# main.net
KiCad netlist of a schematic drawn in Altium Designer
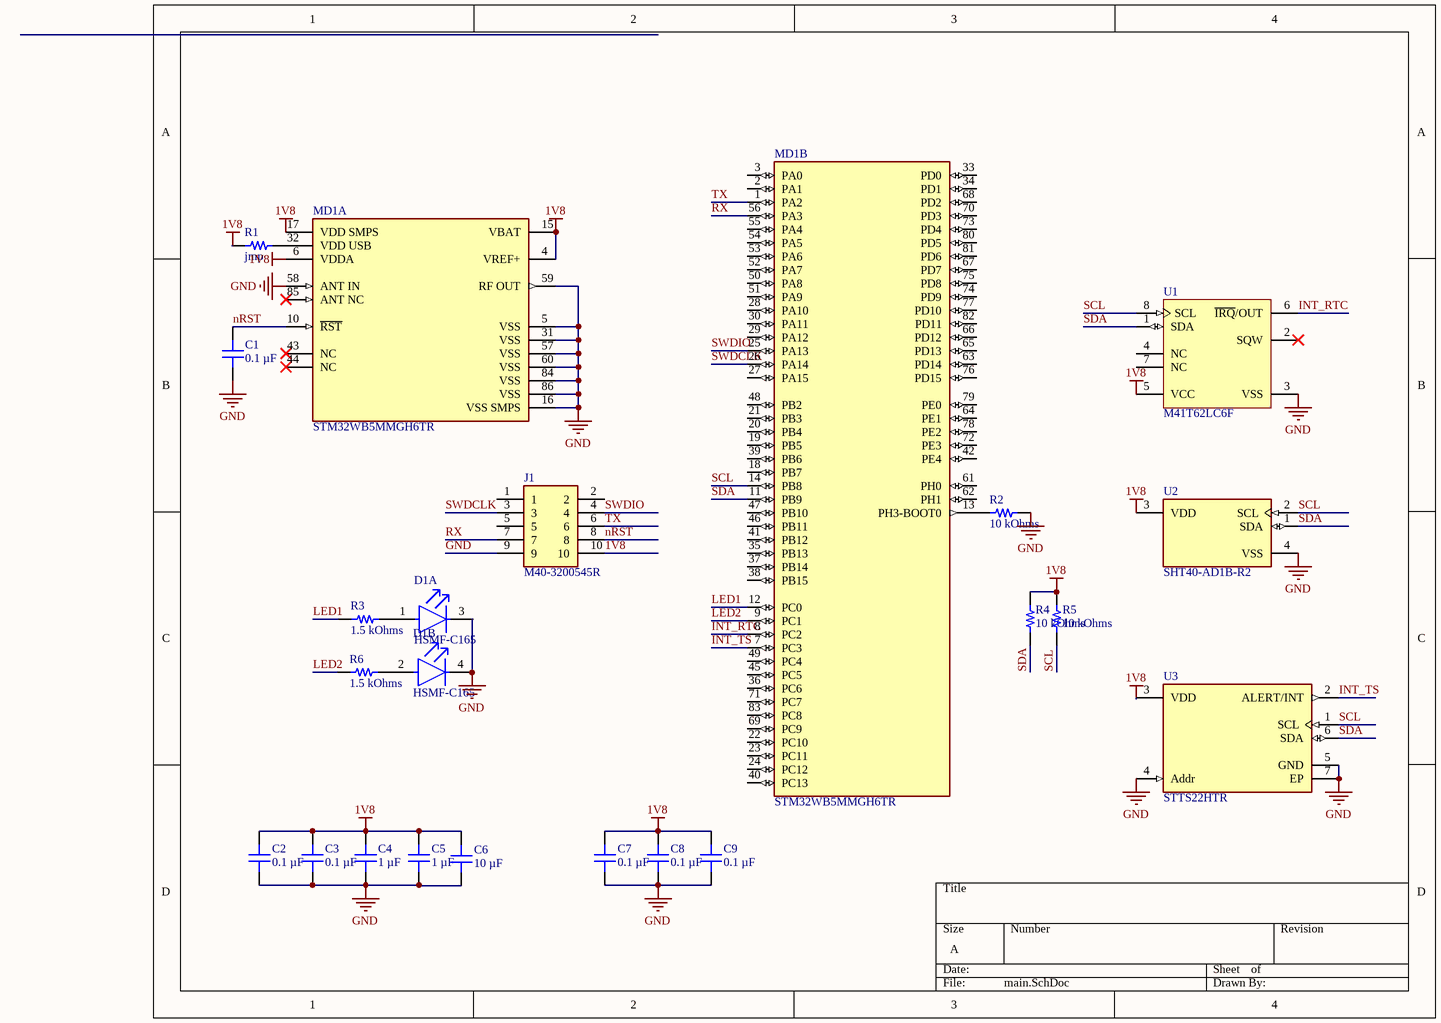
[diagram p0: main.SchDoc]

(export (version "E")
  (design (tool "Eeschema 10.0.6"))
  (components
    (comp (ref "C1")
      (value "0.1 µF")
      (footprint "CAP 0402_1005")
      (description "CAP CER 0.1UF 4V X5R 0402")
      (fields (field (name "PART NUMBER") "C0402C104K7PAC7867") (field (name "MANUFACTURER") "KEMET"))
      (libsource (lib "Celestial Altium Library - altium_library") (part "Capacitor"))
    )
    (comp (ref "C2")
      (value "0.1 µF")
      (footprint "CAP 0402_1005")
      (description "CAP CER 0.1UF 4V X5R 0402")
      (fields (field (name "PART NUMBER") "C0402C104K7PAC7867") (field (name "MANUFACTURER") "KEMET"))
      (libsource (lib "Celestial Altium Library - altium_library") (part "Capacitor"))
    )
    (comp (ref "C3")
      (value "0.1 µF")
      (footprint "CAP 0402_1005")
      (description "CAP CER 0402 0.1UF 16V X7R 10%")
      (fields (field (name "PART NUMBER") "C0402C104K4RECAUTO") (field (name "MANUFACTURER") "KEMET"))
      (libsource (lib "Celestial Altium Library - altium_library") (part "Capacitor"))
    )
    (comp (ref "C4")
      (value "1 µF")
      (footprint "CAP 0402_1005")
      (description "CAP CER 1UF 10V X5R 0402")
      (fields (field (name "PART NUMBER") "LMK105BJ105MVHF") (field (name "MANUFACTURER") "Taiyo Yuden"))
      (libsource (lib "Celestial Altium Library - altium_library") (part "Capacitor"))
    )
    (comp (ref "C5")
      (value "1 µF")
      (footprint "CAP 0402_1005")
      (description "CAP CER 1UF 10V X5R 0402")
      (fields (field (name "PART NUMBER") "LMK105BJ105MVHF") (field (name "MANUFACTURER") "Taiyo Yuden"))
      (libsource (lib "Celestial Altium Library - altium_library") (part "Capacitor"))
    )
    (comp (ref "C6")
      (value "10 µF")
      (footprint "CAP 0603_1608")
      (description "CAP CER 10UF 6.3V X5R 0603")
      (fields
        (field (name "PART NUMBER") "GRM188R60J106ME47D")
        (field (name "MANUFACTURER") "Murata Electronics")
      )
      (libsource (lib "Celestial Altium Library - altium_library") (part "Capacitor"))
    )
    (comp (ref "C7")
      (value "0.1 µF")
      (footprint "CAP 0402_1005")
      (description "CAP CER 0402 0.1UF 16V X7R 10%")
      (fields (field (name "PART NUMBER") "C0402C104K4RECAUTO") (field (name "MANUFACTURER") "KEMET"))
      (libsource (lib "Celestial Altium Library - altium_library") (part "Capacitor"))
    )
    (comp (ref "C8")
      (value "0.1 µF")
      (footprint "CAP 0402_1005")
      (description "CAP CER 0.1UF 4V X5R 0402")
      (fields (field (name "PART NUMBER") "C0402C104K7PAC7867") (field (name "MANUFACTURER") "KEMET"))
      (libsource (lib "Celestial Altium Library - altium_library") (part "Capacitor"))
    )
    (comp (ref "C9")
      (value "0.1 µF")
      (footprint "CAP 0402_1005")
      (description "CAP CER 0.1UF 4V X5R 0402")
      (fields (field (name "PART NUMBER") "C0402C104K7PAC7867") (field (name "MANUFACTURER") "KEMET"))
      (libsource (lib "Celestial Altium Library - altium_library") (part "Capacitor"))
    )
    (comp (ref "D1")
      (value "HSMF-C165")
      (footprint "FP-HSMF-C165-MFG")
      (description "LED GREEN/RED DIFFUSED 0603 SMD")
      (libsource (lib "Altium Content Vault") (part "7c1fe340d8ce6b5db8c50b7ec3493de"))
    )
    (comp (ref "J1")
      (value "M40-3200545R")
      (footprint "HARWIN_M40-3200545R")
      (description "Connector Header Surface Mount 10 position 0.039 _1.00mm_")
      (fields (field (name "MF") "Harwin Inc."))
      (libsource (lib "M40-3200545R") (part "M40-3200545R"))
    )
    (comp (ref "MD1")
      (value "STM32WB5MMGH6TR")
      (footprint "FP-STM32WB5MMGH6TR-MFG")
      (description "ULTRA-LOW-POWER DUAL CORE ARM CO")
      (libsource (lib "Altium Content Vault") (part "634268d29c17b736a8286639810bf7d"))
    )
    (comp (ref "R1")
      (value "jmp")
      (footprint "RES 0402_1005")
      (description "RES 10K OHM 0.1% 1/10W 0402")
      (fields
        (field (name "PART NUMBER") "RP73PF1E10KBTD")
        (field (name "MANUFACTURER") "TE Connectivity Passive Product")
      )
      (libsource (lib "Celestial Altium Library - altium_library") (part "Resistor"))
    )
    (comp (ref "R2")
      (value "10 kOhms")
      (footprint "RES 0402_1005")
      (description "RES 10K OHM 0.1% 1/10W 0402")
      (fields
        (field (name "PART NUMBER") "RP73PF1E10KBTD")
        (field (name "MANUFACTURER") "TE Connectivity Passive Product")
      )
      (libsource (lib "Celestial Altium Library - altium_library") (part "Resistor"))
    )
    (comp (ref "R3")
      (value "1.5 kOhms")
      (footprint "RES 0402_1005")
      (description "RES 1.5K OHM 0.05% 1/10W 0402")
      (fields
        (field (name "PART NUMBER") "ERA-2VRW1501X")
        (field (name "MANUFACTURER") "Panasonic Electronic Components")
      )
      (libsource (lib "Celestial Altium Library - altium_library") (part "Resistor"))
    )
    (comp (ref "R4")
      (value "10 kOhms")
      (footprint "RES 0402_1005")
      (description "RES 10K OHM 0.1% 1/10W 0402")
      (fields
        (field (name "PART NUMBER") "RP73PF1E10KBTD")
        (field (name "MANUFACTURER") "TE Connectivity Passive Product")
      )
      (libsource (lib "Celestial Altium Library - altium_library") (part "Resistor"))
    )
    (comp (ref "R5")
      (value "10 kOhms")
      (footprint "RES 0402_1005")
      (description "RES 10K OHM 0.1% 1/10W 0402")
      (fields
        (field (name "PART NUMBER") "RP73PF1E10KBTD")
        (field (name "MANUFACTURER") "TE Connectivity Passive Product")
      )
      (libsource (lib "Celestial Altium Library - altium_library") (part "Resistor"))
    )
    (comp (ref "R6")
      (value "1.5 kOhms")
      (footprint "RES 0402_1005")
      (description "RES 1.5K OHM 0.05% 1/10W 0402")
      (fields
        (field (name "PART NUMBER") "ERA-2VRW1501X")
        (field (name "MANUFACTURER") "Panasonic Electronic Components")
      )
      (libsource (lib "Celestial Altium Library - altium_library") (part "Resistor"))
    )
    (comp (ref "U1")
      (value "M41T62LC6F")
      (footprint "STM-LCC8_V")
      (fields (field (name "MANUFACTURER") "STMicroelectronics"))
      (libsource (lib "Altium Content Vault") (part "STM-M41T62-LCC8"))
    )
    (comp (ref "U2")
      (value "SHT40-AD1B-R2")
      (footprint "FP-SHT40-AD1B-R2-MFG")
      (description "SENSOR HUMIDITY 100 RH SMD")
      (libsource (lib "Altium Content Vault") (part "985d6b895d3abb4f56b1b691ea450a8"))
    )
    (comp (ref "U3")
      (value "STTS22HTR")
      (footprint "FP-UDFN-6L-DM00423052-MFG")
      (description "LOW-VOLTAGE, ULTRA-LOW-POWER, 0.")
      (fields
        (field (name "OCTOPART") "https://octopart.com/stts22htr-stmicroelectronics-103417944")
        (field (name "MANUFACTURER") "STMicroelectronics")
      )
      (libsource (lib "Altium Content Vault") (part "a8cb2d3fb1f6f6cfa913d99606c4029"))
    )
  )
  (nets
    (net (code "1") (name "/INT_RTC") (class "Default")
      (node (ref "MD1") (pin "8") (pinfunction "PC2_8") (pintype "bidirectional"))
      (node (ref "U1") (pin "6") (pinfunction "~{IRQ}/OUT_6") (pintype "passive"))
    )
    (net (code "2") (name "/INT_TS") (class "Default")
      (node (ref "MD1") (pin "7") (pinfunction "PC3_7") (pintype "bidirectional"))
      (node (ref "U3") (pin "2") (pinfunction "ALERT/INT_2") (pintype "output"))
    )
    (net (code "3") (name "/LED1") (class "Default")
      (node (ref "MD1") (pin "12") (pinfunction "PC0_12") (pintype "bidirectional"))
      (node (ref "R3") (pin "2") (pinfunction "2_2") (pintype "passive"))
    )
    (net (code "4") (name "/LED2") (class "Default")
      (node (ref "MD1") (pin "9") (pinfunction "PC1_9") (pintype "bidirectional"))
      (node (ref "R6") (pin "2") (pinfunction "2_2") (pintype "passive"))
    )
    (net (code "5") (name "/RX") (class "Default")
      (node (ref "J1") (pin "7") (pinfunction "7_7") (pintype "passive"))
      (node (ref "MD1") (pin "56") (pinfunction "PA3_56") (pintype "bidirectional"))
    )
    (net (code "6") (name "/SCL") (class "Default")
      (node (ref "MD1") (pin "14") (pinfunction "PB8_14") (pintype "bidirectional"))
      (node (ref "R5") (pin "2") (pinfunction "2_2") (pintype "passive"))
      (node (ref "U1") (pin "8") (pinfunction "SCL_8") (pintype "input"))
      (node (ref "U2") (pin "2") (pinfunction "SCL_2") (pintype "input"))
      (node (ref "U3") (pin "1") (pinfunction "SCL_1") (pintype "input"))
    )
    (net (code "7") (name "/SDA") (class "Default")
      (node (ref "MD1") (pin "11") (pinfunction "PB9_11") (pintype "bidirectional"))
      (node (ref "R4") (pin "2") (pinfunction "2_2") (pintype "passive"))
      (node (ref "U1") (pin "1") (pinfunction "SDA_1") (pintype "bidirectional"))
      (node (ref "U2") (pin "1") (pinfunction "SDA_1") (pintype "bidirectional"))
      (node (ref "U3") (pin "6") (pinfunction "SDA_6") (pintype "bidirectional"))
    )
    (net (code "8") (name "/SWDCLK") (class "Default")
      (node (ref "J1") (pin "3") (pinfunction "3_3") (pintype "passive"))
      (node (ref "MD1") (pin "26") (pinfunction "PA14_26") (pintype "bidirectional"))
    )
    (net (code "9") (name "/SWDIO") (class "Default")
      (node (ref "J1") (pin "4") (pinfunction "4_4") (pintype "passive"))
      (node (ref "MD1") (pin "25") (pinfunction "PA13_25") (pintype "bidirectional"))
    )
    (net (code "10") (name "/TX") (class "Default")
      (node (ref "J1") (pin "6") (pinfunction "6_6") (pintype "passive"))
      (node (ref "MD1") (pin "1") (pinfunction "PA2_1") (pintype "bidirectional"))
    )
    (net (code "11") (name "/nRST") (class "Default")
      (node (ref "C1") (pin "1") (pinfunction "1_1") (pintype "passive"))
      (node (ref "J1") (pin "8") (pinfunction "8_8") (pintype "passive"))
      (node (ref "MD1") (pin "10") (pinfunction "~{RST}_10") (pintype "input"))
    )
    (net (code "12") (name "1V8") (class "Default")
      (node (ref "C2") (pin "2") (pinfunction "2_2") (pintype "passive"))
      (node (ref "C3") (pin "2") (pinfunction "2_2") (pintype "passive"))
      (node (ref "C4") (pin "2") (pinfunction "2_2") (pintype "passive"))
      (node (ref "C5") (pin "2") (pinfunction "2_2") (pintype "passive"))
      (node (ref "C6") (pin "2") (pinfunction "2_2") (pintype "passive"))
      (node (ref "C7") (pin "2") (pinfunction "2_2") (pintype "passive"))
      (node (ref "C8") (pin "2") (pinfunction "2_2") (pintype "passive"))
      (node (ref "C9") (pin "2") (pinfunction "2_2") (pintype "passive"))
      (node (ref "J1") (pin "10") (pinfunction "10_10") (pintype "passive"))
      (node (ref "MD1") (pin "15") (pinfunction "VBAT_15") (pintype "power_in"))
      (node (ref "MD1") (pin "17") (pinfunction "VDD_SMPS_17") (pintype "power_in"))
      (node (ref "MD1") (pin "4") (pinfunction "VREF+_4") (pintype "power_in"))
      (node (ref "MD1") (pin "6") (pinfunction "VDDA_6") (pintype "power_in"))
      (node (ref "R1") (pin "1") (pinfunction "1_1") (pintype "passive"))
      (node (ref "R4") (pin "1") (pinfunction "1_1") (pintype "passive"))
      (node (ref "R5") (pin "1") (pinfunction "1_1") (pintype "passive"))
      (node (ref "U1") (pin "5") (pinfunction "VCC_5") (pintype "power_in"))
      (node (ref "U2") (pin "3") (pinfunction "VDD_3") (pintype "power_in"))
      (node (ref "U3") (pin "3") (pinfunction "VDD_3") (pintype "power_in"))
    )
    (net (code "13") (name "GND") (class "Default")
      (node (ref "C1") (pin "2") (pinfunction "2_2") (pintype "passive"))
      (node (ref "C2") (pin "1") (pinfunction "1_1") (pintype "passive"))
      (node (ref "C3") (pin "1") (pinfunction "1_1") (pintype "passive"))
      (node (ref "C4") (pin "1") (pinfunction "1_1") (pintype "passive"))
      (node (ref "C5") (pin "1") (pinfunction "1_1") (pintype "passive"))
      (node (ref "C6") (pin "1") (pinfunction "1_1") (pintype "passive"))
      (node (ref "C7") (pin "1") (pinfunction "1_1") (pintype "passive"))
      (node (ref "C8") (pin "1") (pinfunction "1_1") (pintype "passive"))
      (node (ref "C9") (pin "1") (pinfunction "1_1") (pintype "passive"))
      (node (ref "D1") (pin "4") (pinfunction "RED_C_4") (pintype "passive"))
      (node (ref "J1") (pin "9") (pinfunction "9_9") (pintype "passive"))
      (node (ref "MD1") (pin "16") (pinfunction "VSS_SMPS_16") (pintype "power_in"))
      (node (ref "MD1") (pin "31") (pinfunction "VSS_31") (pintype "power_in"))
      (node (ref "MD1") (pin "5") (pinfunction "VSS_5") (pintype "power_in"))
      (node (ref "MD1") (pin "57") (pinfunction "VSS_57") (pintype "power_in"))
      (node (ref "MD1") (pin "58") (pinfunction "ANT_IN_58") (pintype "input"))
      (node (ref "MD1") (pin "59") (pinfunction "RF_OUT_59") (pintype "output"))
      (node (ref "MD1") (pin "60") (pinfunction "VSS_60") (pintype "power_in"))
      (node (ref "MD1") (pin "84") (pinfunction "VSS_84") (pintype "power_in"))
      (node (ref "MD1") (pin "86") (pinfunction "VSS_86") (pintype "power_in"))
      (node (ref "R2") (pin "1") (pinfunction "1_1") (pintype "passive"))
      (node (ref "U1") (pin "3") (pinfunction "VSS_3") (pintype "power_in"))
      (node (ref "U2") (pin "4") (pinfunction "VSS_4") (pintype "power_in"))
      (node (ref "U3") (pin "4") (pinfunction "Addr_4") (pintype "input"))
      (node (ref "U3") (pin "5") (pinfunction "GND_5") (pintype "power_in"))
      (node (ref "U3") (pin "7") (pinfunction "EP_7") (pintype "passive"))
    )
    (net (code "14") (name "Net-(D1A-GREEN_A)") (class "Default")
      (node (ref "D1") (pin "1") (pinfunction "GREEN_A_1") (pintype "passive"))
      (node (ref "R3") (pin "1") (pinfunction "1_1") (pintype "passive"))
    )
    (net (code "15") (name "Net-(D1B-RED_A)") (class "Default")
      (node (ref "D1") (pin "2") (pinfunction "RED_A_2") (pintype "passive"))
      (node (ref "R6") (pin "1") (pinfunction "1_1") (pintype "passive"))
    )
    (net (code "16") (name "Net-(MD1A-VDD_USB)") (class "Default")
      (node (ref "MD1") (pin "32") (pinfunction "VDD_USB_32") (pintype "power_in"))
      (node (ref "R1") (pin "2") (pinfunction "2_2") (pintype "passive"))
    )
    (net (code "17") (name "Net-(MD1B-PH3-BOOT0)") (class "Default")
      (node (ref "MD1") (pin "13") (pinfunction "PH3-BOOT0_13") (pintype "output"))
      (node (ref "R2") (pin "2") (pinfunction "2_2") (pintype "passive"))
    )
    (net (code "18") (name "unconnected-(D1A-GREEN_C-Pad3)") (class "Default")
      (node (ref "D1") (pin "3") (pinfunction "GREEN_C_3") (pintype "passive"))
    )
    (net (code "19") (name "unconnected-(J1-Pad1)") (class "Default")
      (node (ref "J1") (pin "1") (pinfunction "1_1") (pintype "passive"))
    )
    (net (code "20") (name "unconnected-(J1-Pad2)") (class "Default")
      (node (ref "J1") (pin "2") (pinfunction "2_2") (pintype "passive"))
    )
    (net (code "21") (name "unconnected-(J1-Pad5)") (class "Default")
      (node (ref "J1") (pin "5") (pinfunction "5_5") (pintype "passive"))
    )
    (net (code "22") (name "unconnected-(MD1A-ANT_NC-Pad85)") (class "Default")
      (node (ref "MD1") (pin "85") (pinfunction "ANT_NC_85") (pintype "input+no_connect"))
    )
    (net (code "23") (name "unconnected-(MD1A-NC-Pad43)") (class "Default")
      (node (ref "MD1") (pin "43") (pinfunction "NC_43") (pintype "passive+no_connect"))
    )
    (net (code "24") (name "unconnected-(MD1A-NC-Pad44)") (class "Default")
      (node (ref "MD1") (pin "44") (pinfunction "NC_44") (pintype "passive+no_connect"))
    )
    (net (code "25") (name "unconnected-(MD1B-PA0-Pad3)") (class "Default")
      (node (ref "MD1") (pin "3") (pinfunction "PA0_3") (pintype "bidirectional"))
    )
    (net (code "26") (name "unconnected-(MD1B-PA1-Pad2)") (class "Default")
      (node (ref "MD1") (pin "2") (pinfunction "PA1_2") (pintype "bidirectional"))
    )
    (net (code "27") (name "unconnected-(MD1B-PA4-Pad55)") (class "Default")
      (node (ref "MD1") (pin "55") (pinfunction "PA4_55") (pintype "bidirectional"))
    )
    (net (code "28") (name "unconnected-(MD1B-PA5-Pad54)") (class "Default")
      (node (ref "MD1") (pin "54") (pinfunction "PA5_54") (pintype "bidirectional"))
    )
    (net (code "29") (name "unconnected-(MD1B-PA6-Pad53)") (class "Default")
      (node (ref "MD1") (pin "53") (pinfunction "PA6_53") (pintype "bidirectional"))
    )
    (net (code "30") (name "unconnected-(MD1B-PA7-Pad52)") (class "Default")
      (node (ref "MD1") (pin "52") (pinfunction "PA7_52") (pintype "bidirectional"))
    )
    (net (code "31") (name "unconnected-(MD1B-PA8-Pad50)") (class "Default")
      (node (ref "MD1") (pin "50") (pinfunction "PA8_50") (pintype "bidirectional"))
    )
    (net (code "32") (name "unconnected-(MD1B-PA9-Pad51)") (class "Default")
      (node (ref "MD1") (pin "51") (pinfunction "PA9_51") (pintype "bidirectional"))
    )
    (net (code "33") (name "unconnected-(MD1B-PA10-Pad28)") (class "Default")
      (node (ref "MD1") (pin "28") (pinfunction "PA10_28") (pintype "bidirectional"))
    )
    (net (code "34") (name "unconnected-(MD1B-PA11-Pad30)") (class "Default")
      (node (ref "MD1") (pin "30") (pinfunction "PA11_30") (pintype "bidirectional"))
    )
    (net (code "35") (name "unconnected-(MD1B-PA12-Pad29)") (class "Default")
      (node (ref "MD1") (pin "29") (pinfunction "PA12_29") (pintype "bidirectional"))
    )
    (net (code "36") (name "unconnected-(MD1B-PA15-Pad27)") (class "Default")
      (node (ref "MD1") (pin "27") (pinfunction "PA15_27") (pintype "bidirectional"))
    )
    (net (code "37") (name "unconnected-(MD1B-PB2-Pad48)") (class "Default")
      (node (ref "MD1") (pin "48") (pinfunction "PB2_48") (pintype "bidirectional"))
    )
    (net (code "38") (name "unconnected-(MD1B-PB3-Pad21)") (class "Default")
      (node (ref "MD1") (pin "21") (pinfunction "PB3_21") (pintype "bidirectional"))
    )
    (net (code "39") (name "unconnected-(MD1B-PB4-Pad20)") (class "Default")
      (node (ref "MD1") (pin "20") (pinfunction "PB4_20") (pintype "bidirectional"))
    )
    (net (code "40") (name "unconnected-(MD1B-PB5-Pad19)") (class "Default")
      (node (ref "MD1") (pin "19") (pinfunction "PB5_19") (pintype "bidirectional"))
    )
    (net (code "41") (name "unconnected-(MD1B-PB6-Pad39)") (class "Default")
      (node (ref "MD1") (pin "39") (pinfunction "PB6_39") (pintype "bidirectional"))
    )
    (net (code "42") (name "unconnected-(MD1B-PB7-Pad18)") (class "Default")
      (node (ref "MD1") (pin "18") (pinfunction "PB7_18") (pintype "bidirectional"))
    )
    (net (code "43") (name "unconnected-(MD1B-PB10-Pad47)") (class "Default")
      (node (ref "MD1") (pin "47") (pinfunction "PB10_47") (pintype "bidirectional"))
    )
    (net (code "44") (name "unconnected-(MD1B-PB11-Pad46)") (class "Default")
      (node (ref "MD1") (pin "46") (pinfunction "PB11_46") (pintype "bidirectional"))
    )
    (net (code "45") (name "unconnected-(MD1B-PB12-Pad41)") (class "Default")
      (node (ref "MD1") (pin "41") (pinfunction "PB12_41") (pintype "bidirectional"))
    )
    (net (code "46") (name "unconnected-(MD1B-PB13-Pad35)") (class "Default")
      (node (ref "MD1") (pin "35") (pinfunction "PB13_35") (pintype "bidirectional"))
    )
    (net (code "47") (name "unconnected-(MD1B-PB14-Pad37)") (class "Default")
      (node (ref "MD1") (pin "37") (pinfunction "PB14_37") (pintype "bidirectional"))
    )
    (net (code "48") (name "unconnected-(MD1B-PB15-Pad38)") (class "Default")
      (node (ref "MD1") (pin "38") (pinfunction "PB15_38") (pintype "bidirectional"))
    )
    (net (code "49") (name "unconnected-(MD1B-PC4-Pad49)") (class "Default")
      (node (ref "MD1") (pin "49") (pinfunction "PC4_49") (pintype "bidirectional"))
    )
    (net (code "50") (name "unconnected-(MD1B-PC5-Pad45)") (class "Default")
      (node (ref "MD1") (pin "45") (pinfunction "PC5_45") (pintype "bidirectional"))
    )
    (net (code "51") (name "unconnected-(MD1B-PC6-Pad36)") (class "Default")
      (node (ref "MD1") (pin "36") (pinfunction "PC6_36") (pintype "bidirectional"))
    )
    (net (code "52") (name "unconnected-(MD1B-PC7-Pad71)") (class "Default")
      (node (ref "MD1") (pin "71") (pinfunction "PC7_71") (pintype "bidirectional"))
    )
    (net (code "53") (name "unconnected-(MD1B-PC8-Pad83)") (class "Default")
      (node (ref "MD1") (pin "83") (pinfunction "PC8_83") (pintype "bidirectional"))
    )
    (net (code "54") (name "unconnected-(MD1B-PC9-Pad69)") (class "Default")
      (node (ref "MD1") (pin "69") (pinfunction "PC9_69") (pintype "bidirectional"))
    )
    (net (code "55") (name "unconnected-(MD1B-PC10-Pad22)") (class "Default")
      (node (ref "MD1") (pin "22") (pinfunction "PC10_22") (pintype "bidirectional"))
    )
    (net (code "56") (name "unconnected-(MD1B-PC11-Pad23)") (class "Default")
      (node (ref "MD1") (pin "23") (pinfunction "PC11_23") (pintype "bidirectional"))
    )
    (net (code "57") (name "unconnected-(MD1B-PC12-Pad24)") (class "Default")
      (node (ref "MD1") (pin "24") (pinfunction "PC12_24") (pintype "bidirectional"))
    )
    (net (code "58") (name "unconnected-(MD1B-PC13-Pad40)") (class "Default")
      (node (ref "MD1") (pin "40") (pinfunction "PC13_40") (pintype "bidirectional"))
    )
    (net (code "59") (name "unconnected-(MD1B-PD0-Pad33)") (class "Default")
      (node (ref "MD1") (pin "33") (pinfunction "PD0_33") (pintype "bidirectional"))
    )
    (net (code "60") (name "unconnected-(MD1B-PD1-Pad34)") (class "Default")
      (node (ref "MD1") (pin "34") (pinfunction "PD1_34") (pintype "bidirectional"))
    )
    (net (code "61") (name "unconnected-(MD1B-PD2-Pad68)") (class "Default")
      (node (ref "MD1") (pin "68") (pinfunction "PD2_68") (pintype "bidirectional"))
    )
    (net (code "62") (name "unconnected-(MD1B-PD3-Pad70)") (class "Default")
      (node (ref "MD1") (pin "70") (pinfunction "PD3_70") (pintype "bidirectional"))
    )
    (net (code "63") (name "unconnected-(MD1B-PD4-Pad73)") (class "Default")
      (node (ref "MD1") (pin "73") (pinfunction "PD4_73") (pintype "bidirectional"))
    )
    (net (code "64") (name "unconnected-(MD1B-PD5-Pad80)") (class "Default")
      (node (ref "MD1") (pin "80") (pinfunction "PD5_80") (pintype "bidirectional"))
    )
    (net (code "65") (name "unconnected-(MD1B-PD6-Pad81)") (class "Default")
      (node (ref "MD1") (pin "81") (pinfunction "PD6_81") (pintype "bidirectional"))
    )
    (net (code "66") (name "unconnected-(MD1B-PD7-Pad67)") (class "Default")
      (node (ref "MD1") (pin "67") (pinfunction "PD7_67") (pintype "bidirectional"))
    )
    (net (code "67") (name "unconnected-(MD1B-PD8-Pad75)") (class "Default")
      (node (ref "MD1") (pin "75") (pinfunction "PD8_75") (pintype "bidirectional"))
    )
    (net (code "68") (name "unconnected-(MD1B-PD9-Pad74)") (class "Default")
      (node (ref "MD1") (pin "74") (pinfunction "PD9_74") (pintype "bidirectional"))
    )
    (net (code "69") (name "unconnected-(MD1B-PD10-Pad77)") (class "Default")
      (node (ref "MD1") (pin "77") (pinfunction "PD10_77") (pintype "bidirectional"))
    )
    (net (code "70") (name "unconnected-(MD1B-PD11-Pad82)") (class "Default")
      (node (ref "MD1") (pin "82") (pinfunction "PD11_82") (pintype "bidirectional"))
    )
    (net (code "71") (name "unconnected-(MD1B-PD12-Pad66)") (class "Default")
      (node (ref "MD1") (pin "66") (pinfunction "PD12_66") (pintype "bidirectional"))
    )
    (net (code "72") (name "unconnected-(MD1B-PD13-Pad65)") (class "Default")
      (node (ref "MD1") (pin "65") (pinfunction "PD13_65") (pintype "bidirectional"))
    )
    (net (code "73") (name "unconnected-(MD1B-PD14-Pad63)") (class "Default")
      (node (ref "MD1") (pin "63") (pinfunction "PD14_63") (pintype "bidirectional"))
    )
    (net (code "74") (name "unconnected-(MD1B-PD15-Pad76)") (class "Default")
      (node (ref "MD1") (pin "76") (pinfunction "PD15_76") (pintype "bidirectional"))
    )
    (net (code "75") (name "unconnected-(MD1B-PE0-Pad79)") (class "Default")
      (node (ref "MD1") (pin "79") (pinfunction "PE0_79") (pintype "bidirectional"))
    )
    (net (code "76") (name "unconnected-(MD1B-PE1-Pad64)") (class "Default")
      (node (ref "MD1") (pin "64") (pinfunction "PE1_64") (pintype "bidirectional"))
    )
    (net (code "77") (name "unconnected-(MD1B-PE2-Pad78)") (class "Default")
      (node (ref "MD1") (pin "78") (pinfunction "PE2_78") (pintype "bidirectional"))
    )
    (net (code "78") (name "unconnected-(MD1B-PE3-Pad72)") (class "Default")
      (node (ref "MD1") (pin "72") (pinfunction "PE3_72") (pintype "bidirectional"))
    )
    (net (code "79") (name "unconnected-(MD1B-PE4-Pad42)") (class "Default")
      (node (ref "MD1") (pin "42") (pinfunction "PE4_42") (pintype "bidirectional"))
    )
    (net (code "80") (name "unconnected-(MD1B-PH0-Pad61)") (class "Default")
      (node (ref "MD1") (pin "61") (pinfunction "PH0_61") (pintype "bidirectional"))
    )
    (net (code "81") (name "unconnected-(MD1B-PH1-Pad62)") (class "Default")
      (node (ref "MD1") (pin "62") (pinfunction "PH1_62") (pintype "bidirectional"))
    )
    (net (code "82") (name "unconnected-(U1-NC-Pad4)") (class "Default")
      (node (ref "U1") (pin "4") (pinfunction "NC_4") (pintype "passive"))
    )
    (net (code "83") (name "unconnected-(U1-NC-Pad7)") (class "Default")
      (node (ref "U1") (pin "7") (pinfunction "NC_7") (pintype "passive"))
    )
    (net (code "84") (name "unconnected-(U1-SQW-Pad2)") (class "Default")
      (node (ref "U1") (pin "2") (pinfunction "SQW_2") (pintype "passive+no_connect"))
    )
  )
)
